# output.net
KiCad netlist of a schematic drawn in Altium Designer
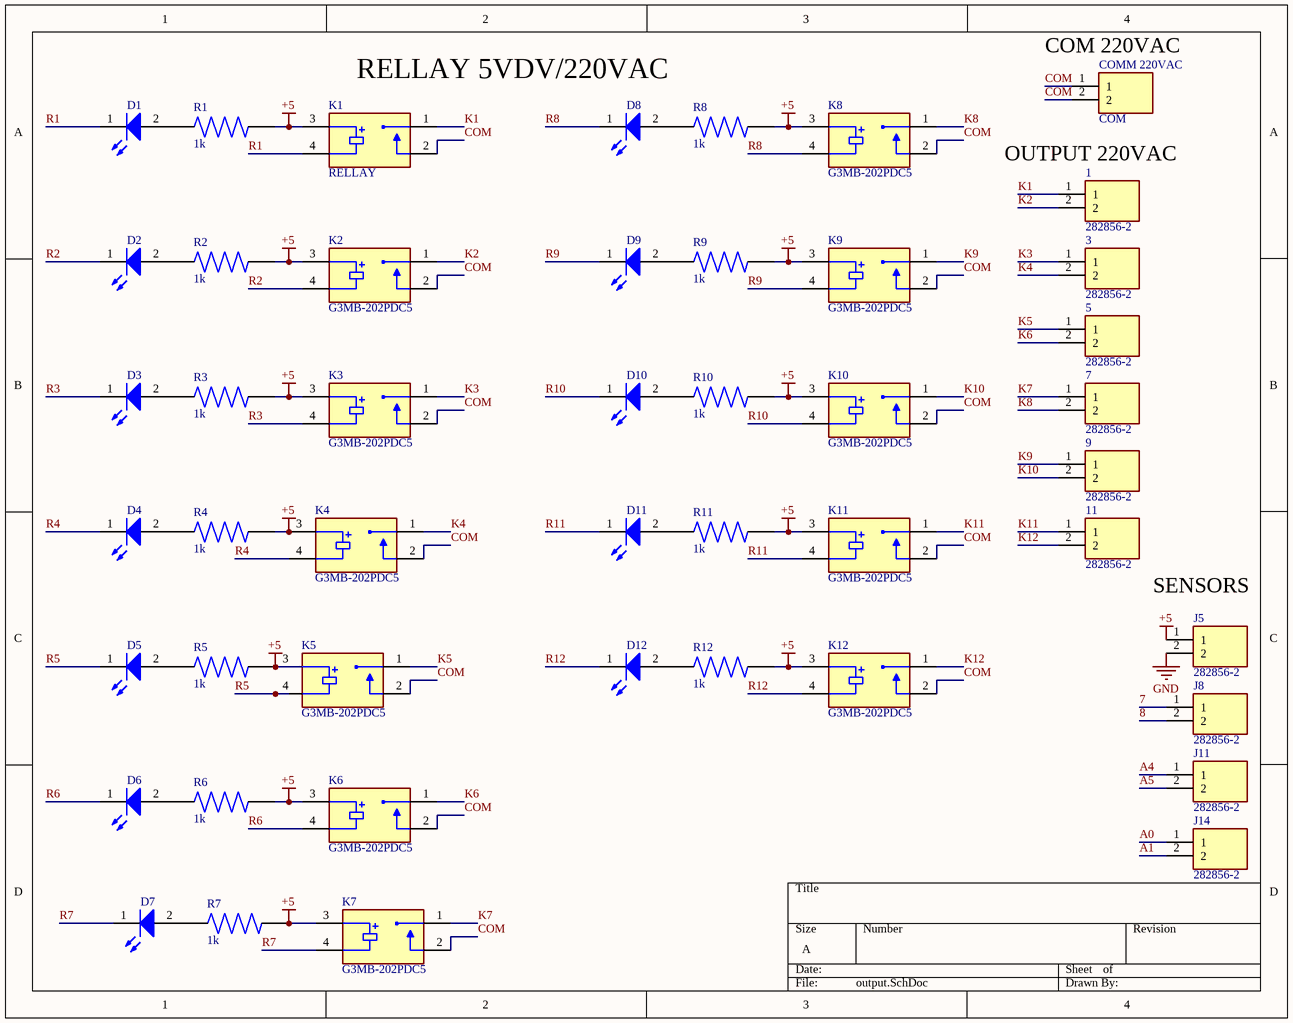
[diagram p0: output.SchDoc]

(export (version "E")
  (design (tool "Eeschema 10.0.6"))
  (components
    (comp (ref "1")
      (value "282856-2")
      (footprint "TE_282856-2")
      (description "TERMI-BLOK PCB MOUNT 2P")
      (fields (field (name "MF") "TE Connectivity"))
      (libsource (lib "input") (part "282856-2"))
    )
    (comp (ref "3")
      (value "282856-2")
      (footprint "TE_282856-2")
      (description "TERMI-BLOK PCB MOUNT 2P")
      (fields (field (name "MF") "TE Connectivity"))
      (libsource (lib "input") (part "282856-2"))
    )
    (comp (ref "5")
      (value "282856-2")
      (footprint "TE_282856-2")
      (description "TERMI-BLOK PCB MOUNT 2P")
      (fields (field (name "MF") "TE Connectivity"))
      (libsource (lib "input") (part "282856-2"))
    )
    (comp (ref "7")
      (value "282856-2")
      (footprint "TE_282856-2")
      (description "TERMI-BLOK PCB MOUNT 2P")
      (fields (field (name "MF") "TE Connectivity"))
      (libsource (lib "input") (part "282856-2"))
    )
    (comp (ref "9")
      (value "282856-2")
      (footprint "TE_282856-2")
      (description "TERMI-BLOK PCB MOUNT 2P")
      (fields (field (name "MF") "TE Connectivity"))
      (libsource (lib "input") (part "282856-2"))
    )
    (comp (ref "11")
      (value "282856-2")
      (footprint "TE_282856-2")
      (description "TERMI-BLOK PCB MOUNT 2P")
      (fields (field (name "MF") "TE Connectivity"))
      (libsource (lib "input") (part "282856-2"))
    )
    (comp (ref "COMM 220VAC")
      (value "COM")
      (footprint "TE_282856-2")
      (description "TERMI-BLOK PCB MOUNT 2P")
      (fields (field (name "MP") "282856-2") (field (name "MF") "TE Connectivity"))
      (libsource (lib "input") (part "282856-2"))
    )
    (comp (ref "D1")
      (value "Infrared, 1.4V, 140°")
      (footprint "WL-SICW_0805_L2W1.3H0.8")
      (description "WL-SICW SMT Chip LED Infrared Waterclear, size 0805, Infrared, 1.4V, 140°")
      (fields
        (field (name "MANUFACTURER PART NUMBER") "15408085BA400")
        (field (name "MANUFACTURER") "Wurth Elektronik")
      )
      (libsource (lib "input") (part "15408085BA400"))
    )
    (comp (ref "D2")
      (value "Infrared, 1.4V, 140°")
      (footprint "WL-SICW_0805_L2W1.3H0.8")
      (description "WL-SICW SMT Chip LED Infrared Waterclear, size 0805, Infrared, 1.4V, 140°")
      (fields
        (field (name "MANUFACTURER PART NUMBER") "15408085BA400")
        (field (name "MANUFACTURER") "Wurth Elektronik")
      )
      (libsource (lib "input") (part "15408085BA400"))
    )
    (comp (ref "D3")
      (value "Infrared, 1.4V, 140°")
      (footprint "WL-SICW_0805_L2W1.3H0.8")
      (description "WL-SICW SMT Chip LED Infrared Waterclear, size 0805, Infrared, 1.4V, 140°")
      (fields
        (field (name "MANUFACTURER PART NUMBER") "15408085BA400")
        (field (name "MANUFACTURER") "Wurth Elektronik")
      )
      (libsource (lib "input") (part "15408085BA400"))
    )
    (comp (ref "D4")
      (value "Infrared, 1.4V, 140°")
      (footprint "WL-SICW_0805_L2W1.3H0.8")
      (description "WL-SICW SMT Chip LED Infrared Waterclear, size 0805, Infrared, 1.4V, 140°")
      (fields
        (field (name "MANUFACTURER PART NUMBER") "15408085BA400")
        (field (name "MANUFACTURER") "Wurth Elektronik")
      )
      (libsource (lib "input") (part "15408085BA400"))
    )
    (comp (ref "D5")
      (value "Infrared, 1.4V, 140°")
      (footprint "WL-SICW_0805_L2W1.3H0.8")
      (description "WL-SICW SMT Chip LED Infrared Waterclear, size 0805, Infrared, 1.4V, 140°")
      (fields
        (field (name "MANUFACTURER PART NUMBER") "15408085BA400")
        (field (name "MANUFACTURER") "Wurth Elektronik")
      )
      (libsource (lib "input") (part "15408085BA400"))
    )
    (comp (ref "D6")
      (value "Infrared, 1.4V, 140°")
      (footprint "WL-SICW_0805_L2W1.3H0.8")
      (description "WL-SICW SMT Chip LED Infrared Waterclear, size 0805, Infrared, 1.4V, 140°")
      (fields
        (field (name "MANUFACTURER PART NUMBER") "15408085BA400")
        (field (name "MANUFACTURER") "Wurth Elektronik")
      )
      (libsource (lib "input") (part "15408085BA400"))
    )
    (comp (ref "D7")
      (value "Infrared, 1.4V, 140°")
      (footprint "WL-SICW_0805_L2W1.3H0.8")
      (description "WL-SICW SMT Chip LED Infrared Waterclear, size 0805, Infrared, 1.4V, 140°")
      (fields
        (field (name "MANUFACTURER PART NUMBER") "15408085BA400")
        (field (name "MANUFACTURER") "Wurth Elektronik")
      )
      (libsource (lib "input") (part "15408085BA400"))
    )
    (comp (ref "D8")
      (value "Infrared, 1.4V, 140°")
      (footprint "WL-SICW_0805_L2W1.3H0.8")
      (description "WL-SICW SMT Chip LED Infrared Waterclear, size 0805, Infrared, 1.4V, 140°")
      (fields
        (field (name "MANUFACTURER PART NUMBER") "15408085BA400")
        (field (name "MANUFACTURER") "Wurth Elektronik")
      )
      (libsource (lib "input") (part "15408085BA400"))
    )
    (comp (ref "D9")
      (value "Infrared, 1.4V, 140°")
      (footprint "WL-SICW_0805_L2W1.3H0.8")
      (description "WL-SICW SMT Chip LED Infrared Waterclear, size 0805, Infrared, 1.4V, 140°")
      (fields
        (field (name "MANUFACTURER PART NUMBER") "15408085BA400")
        (field (name "MANUFACTURER") "Wurth Elektronik")
      )
      (libsource (lib "input") (part "15408085BA400"))
    )
    (comp (ref "D10")
      (value "Infrared, 1.4V, 140°")
      (footprint "WL-SICW_0805_L2W1.3H0.8")
      (description "WL-SICW SMT Chip LED Infrared Waterclear, size 0805, Infrared, 1.4V, 140°")
      (fields
        (field (name "MANUFACTURER PART NUMBER") "15408085BA400")
        (field (name "MANUFACTURER") "Wurth Elektronik")
      )
      (libsource (lib "input") (part "15408085BA400"))
    )
    (comp (ref "D11")
      (value "Infrared, 1.4V, 140°")
      (footprint "WL-SICW_0805_L2W1.3H0.8")
      (description "WL-SICW SMT Chip LED Infrared Waterclear, size 0805, Infrared, 1.4V, 140°")
      (fields
        (field (name "MANUFACTURER PART NUMBER") "15408085BA400")
        (field (name "MANUFACTURER") "Wurth Elektronik")
      )
      (libsource (lib "input") (part "15408085BA400"))
    )
    (comp (ref "D12")
      (value "Infrared, 1.4V, 140°")
      (footprint "WL-SICW_0805_L2W1.3H0.8")
      (description "WL-SICW SMT Chip LED Infrared Waterclear, size 0805, Infrared, 1.4V, 140°")
      (fields
        (field (name "MANUFACTURER PART NUMBER") "15408085BA400")
        (field (name "MANUFACTURER") "Wurth Elektronik")
      )
      (libsource (lib "input") (part "15408085BA400"))
    )
    (comp (ref "J5")
      (value "282856-2")
      (footprint "TE_282856-2")
      (description "TERMI-BLOK PCB MOUNT 2P")
      (fields (field (name "MF") "TE Connectivity"))
      (libsource (lib "input") (part "282856-2"))
    )
    (comp (ref "J8")
      (value "282856-2")
      (footprint "TE_282856-2")
      (description "TERMI-BLOK PCB MOUNT 2P")
      (fields (field (name "MF") "TE Connectivity"))
      (libsource (lib "input") (part "282856-2"))
    )
    (comp (ref "J11")
      (value "282856-2")
      (footprint "TE_282856-2")
      (description "TERMI-BLOK PCB MOUNT 2P")
      (fields (field (name "MF") "TE Connectivity"))
      (libsource (lib "input") (part "282856-2"))
    )
    (comp (ref "J14")
      (value "282856-2")
      (footprint "TE_282856-2")
      (description "TERMI-BLOK PCB MOUNT 2P")
      (fields (field (name "MF") "TE Connectivity"))
      (libsource (lib "input") (part "282856-2"))
    )
    (comp (ref "K1")
      (value "RELLAY")
      (footprint "control:RELAY_G3MB-202PDC5")
      (description "Solid State SPST-NO (1 Form A) 4-SIP")
      (fields (field (name "MP") "G3MB-202P DC5") (field (name "MF") "Omron Automation"))
      (libsource (lib "control") (part "G3MB-202PDC5"))
    )
    (comp (ref "K2")
      (value "G3MB-202PDC5")
      (footprint "control:RELAY_G3MB-202PDC5")
      (description "Solid State SPST-NO (1 Form A) 4-SIP")
      (fields (field (name "MP") "G3MB-202P DC5") (field (name "MF") "Omron Automation"))
      (libsource (lib "control") (part "G3MB-202PDC5"))
    )
    (comp (ref "K3")
      (value "G3MB-202PDC5")
      (footprint "control:RELAY_G3MB-202PDC5")
      (description "Solid State SPST-NO (1 Form A) 4-SIP")
      (fields (field (name "MP") "G3MB-202P DC5") (field (name "MF") "Omron Automation"))
      (libsource (lib "control") (part "G3MB-202PDC5"))
    )
    (comp (ref "K4")
      (value "G3MB-202PDC5")
      (footprint "control:RELAY_G3MB-202PDC5")
      (description "Solid State SPST-NO (1 Form A) 4-SIP")
      (fields (field (name "MP") "G3MB-202P DC5") (field (name "MF") "Omron Automation"))
      (libsource (lib "control") (part "G3MB-202PDC5"))
    )
    (comp (ref "K5")
      (value "G3MB-202PDC5")
      (footprint "control:RELAY_G3MB-202PDC5")
      (description "Solid State SPST-NO (1 Form A) 4-SIP")
      (fields (field (name "MP") "G3MB-202P DC5") (field (name "MF") "Omron Automation"))
      (libsource (lib "control") (part "G3MB-202PDC5"))
    )
    (comp (ref "K6")
      (value "G3MB-202PDC5")
      (footprint "control:RELAY_G3MB-202PDC5")
      (description "Solid State SPST-NO (1 Form A) 4-SIP")
      (fields (field (name "MP") "G3MB-202P DC5") (field (name "MF") "Omron Automation"))
      (libsource (lib "control") (part "G3MB-202PDC5"))
    )
    (comp (ref "K7")
      (value "G3MB-202PDC5")
      (footprint "control:RELAY_G3MB-202PDC5")
      (description "Solid State SPST-NO (1 Form A) 4-SIP")
      (fields (field (name "MP") "G3MB-202P DC5") (field (name "MF") "Omron Automation"))
      (libsource (lib "control") (part "G3MB-202PDC5"))
    )
    (comp (ref "K8")
      (value "G3MB-202PDC5")
      (footprint "control:RELAY_G3MB-202PDC5")
      (description "Solid State SPST-NO (1 Form A) 4-SIP")
      (fields (field (name "MP") "G3MB-202P DC5") (field (name "MF") "Omron Automation"))
      (libsource (lib "control") (part "G3MB-202PDC5"))
    )
    (comp (ref "K9")
      (value "G3MB-202PDC5")
      (footprint "control:RELAY_G3MB-202PDC5")
      (description "Solid State SPST-NO (1 Form A) 4-SIP")
      (fields (field (name "MP") "G3MB-202P DC5") (field (name "MF") "Omron Automation"))
      (libsource (lib "control") (part "G3MB-202PDC5"))
    )
    (comp (ref "K10")
      (value "G3MB-202PDC5")
      (footprint "control:RELAY_G3MB-202PDC5")
      (description "Solid State SPST-NO (1 Form A) 4-SIP")
      (fields (field (name "MP") "G3MB-202P DC5") (field (name "MF") "Omron Automation"))
      (libsource (lib "control") (part "G3MB-202PDC5"))
    )
    (comp (ref "K11")
      (value "G3MB-202PDC5")
      (footprint "control:RELAY_G3MB-202PDC5")
      (description "Solid State SPST-NO (1 Form A) 4-SIP")
      (fields (field (name "MP") "G3MB-202P DC5") (field (name "MF") "Omron Automation"))
      (libsource (lib "control") (part "G3MB-202PDC5"))
    )
    (comp (ref "K12")
      (value "G3MB-202PDC5")
      (footprint "control:RELAY_G3MB-202PDC5")
      (description "Solid State SPST-NO (1 Form A) 4-SIP")
      (fields (field (name "MP") "G3MB-202P DC5") (field (name "MF") "Omron Automation"))
      (libsource (lib "control") (part "G3MB-202PDC5"))
    )
    (comp (ref "R1")
      (value "1k")
      (footprint "RESC3216X70N")
      (description "Res 1206 10 Ohm 5% 1/8W Â±500ppm/Â°C Molded SMD SMD T/R")
      (fields (field (name "TOLERANCE") "5%") (field (name "MP") "FCR1206J10R"))
      (libsource (lib "input") (part "FCR1206J10R"))
    )
    (comp (ref "R2")
      (value "1k")
      (footprint "RESC3216X70N")
      (description "Res 1206 10 Ohm 5% 1/8W Â±500ppm/Â°C Molded SMD SMD T/R")
      (fields (field (name "TOLERANCE") "5%") (field (name "MP") "FCR1206J10R"))
      (libsource (lib "input") (part "FCR1206J10R"))
    )
    (comp (ref "R3")
      (value "1k")
      (footprint "RESC3216X70N")
      (description "Res 1206 10 Ohm 5% 1/8W Â±500ppm/Â°C Molded SMD SMD T/R")
      (fields (field (name "TOLERANCE") "5%") (field (name "MP") "FCR1206J10R"))
      (libsource (lib "input") (part "FCR1206J10R"))
    )
    (comp (ref "R4")
      (value "1k")
      (footprint "RESC3216X70N")
      (description "Res 1206 10 Ohm 5% 1/8W Â±500ppm/Â°C Molded SMD SMD T/R")
      (fields (field (name "TOLERANCE") "5%") (field (name "MP") "FCR1206J10R"))
      (libsource (lib "input") (part "FCR1206J10R"))
    )
    (comp (ref "R5")
      (value "1k")
      (footprint "RESC3216X70N")
      (description "Res 1206 10 Ohm 5% 1/8W Â±500ppm/Â°C Molded SMD SMD T/R")
      (fields (field (name "TOLERANCE") "5%") (field (name "MP") "FCR1206J10R"))
      (libsource (lib "input") (part "FCR1206J10R"))
    )
    (comp (ref "R6")
      (value "1k")
      (footprint "RESC3216X70N")
      (description "Res 1206 10 Ohm 5% 1/8W Â±500ppm/Â°C Molded SMD SMD T/R")
      (fields (field (name "TOLERANCE") "5%") (field (name "MP") "FCR1206J10R"))
      (libsource (lib "input") (part "FCR1206J10R"))
    )
    (comp (ref "R7")
      (value "1k")
      (footprint "RESC3216X70N")
      (description "Res 1206 10 Ohm 5% 1/8W Â±500ppm/Â°C Molded SMD SMD T/R")
      (fields (field (name "TOLERANCE") "5%") (field (name "MP") "FCR1206J10R"))
      (libsource (lib "input") (part "FCR1206J10R"))
    )
    (comp (ref "R8")
      (value "1k")
      (footprint "RESC3216X70N")
      (description "Res 1206 10 Ohm 5% 1/8W Â±500ppm/Â°C Molded SMD SMD T/R")
      (fields (field (name "TOLERANCE") "5%") (field (name "MP") "FCR1206J10R"))
      (libsource (lib "input") (part "FCR1206J10R"))
    )
    (comp (ref "R9")
      (value "1k")
      (footprint "RESC3216X70N")
      (description "Res 1206 10 Ohm 5% 1/8W Â±500ppm/Â°C Molded SMD SMD T/R")
      (fields (field (name "TOLERANCE") "5%") (field (name "MP") "FCR1206J10R"))
      (libsource (lib "input") (part "FCR1206J10R"))
    )
    (comp (ref "R10")
      (value "1k")
      (footprint "RESC3216X70N")
      (description "Res 1206 10 Ohm 5% 1/8W Â±500ppm/Â°C Molded SMD SMD T/R")
      (fields (field (name "TOLERANCE") "5%") (field (name "MP") "FCR1206J10R"))
      (libsource (lib "input") (part "FCR1206J10R"))
    )
    (comp (ref "R11")
      (value "1k")
      (footprint "RESC3216X70N")
      (description "Res 1206 10 Ohm 5% 1/8W Â±500ppm/Â°C Molded SMD SMD T/R")
      (fields (field (name "TOLERANCE") "5%") (field (name "MP") "FCR1206J10R"))
      (libsource (lib "input") (part "FCR1206J10R"))
    )
    (comp (ref "R12")
      (value "1k")
      (footprint "RESC3216X70N")
      (description "Res 1206 10 Ohm 5% 1/8W Â±500ppm/Â°C Molded SMD SMD T/R")
      (fields (field (name "TOLERANCE") "5%") (field (name "MP") "FCR1206J10R"))
      (libsource (lib "input") (part "FCR1206J10R"))
    )
  )
  (nets
    (net (code "1") (name "+5") (class "Default")
      (node (ref "J5") (pin "1") (pinfunction "1_1") (pintype "passive"))
      (node (ref "K1") (pin "3") (pinfunction "3_3") (pintype "passive"))
      (node (ref "K10") (pin "3") (pinfunction "3_3") (pintype "passive"))
      (node (ref "K11") (pin "3") (pinfunction "3_3") (pintype "passive"))
      (node (ref "K12") (pin "3") (pinfunction "3_3") (pintype "passive"))
      (node (ref "K2") (pin "3") (pinfunction "3_3") (pintype "passive"))
      (node (ref "K3") (pin "3") (pinfunction "3_3") (pintype "passive"))
      (node (ref "K4") (pin "3") (pinfunction "3_3") (pintype "passive"))
      (node (ref "K5") (pin "3") (pinfunction "3_3") (pintype "passive"))
      (node (ref "K6") (pin "3") (pinfunction "3_3") (pintype "passive"))
      (node (ref "K7") (pin "3") (pinfunction "3_3") (pintype "passive"))
      (node (ref "K8") (pin "3") (pinfunction "3_3") (pintype "passive"))
      (node (ref "K9") (pin "3") (pinfunction "3_3") (pintype "passive"))
      (node (ref "R1") (pin "2") (pinfunction "2_2") (pintype "passive"))
      (node (ref "R10") (pin "2") (pinfunction "2_2") (pintype "passive"))
      (node (ref "R11") (pin "2") (pinfunction "2_2") (pintype "passive"))
      (node (ref "R12") (pin "2") (pinfunction "2_2") (pintype "passive"))
      (node (ref "R2") (pin "2") (pinfunction "2_2") (pintype "passive"))
      (node (ref "R3") (pin "2") (pinfunction "2_2") (pintype "passive"))
      (node (ref "R4") (pin "2") (pinfunction "2_2") (pintype "passive"))
      (node (ref "R5") (pin "2") (pinfunction "2_2") (pintype "passive"))
      (node (ref "R6") (pin "2") (pinfunction "2_2") (pintype "passive"))
      (node (ref "R7") (pin "2") (pinfunction "2_2") (pintype "passive"))
      (node (ref "R8") (pin "2") (pinfunction "2_2") (pintype "passive"))
      (node (ref "R9") (pin "2") (pinfunction "2_2") (pintype "passive"))
    )
    (net (code "2") (name "/7") (class "Default")
      (node (ref "J8") (pin "1") (pinfunction "1_1") (pintype "passive"))
    )
    (net (code "3") (name "/8") (class "Default")
      (node (ref "J8") (pin "2") (pinfunction "2_2") (pintype "passive"))
    )
    (net (code "4") (name "/A0") (class "Default")
      (node (ref "J14") (pin "1") (pinfunction "1_1") (pintype "passive"))
    )
    (net (code "5") (name "/A1") (class "Default")
      (node (ref "J14") (pin "2") (pinfunction "2_2") (pintype "passive"))
    )
    (net (code "6") (name "/A4") (class "Default")
      (node (ref "J11") (pin "1") (pinfunction "1_1") (pintype "passive"))
    )
    (net (code "7") (name "/A5") (class "Default")
      (node (ref "J11") (pin "2") (pinfunction "2_2") (pintype "passive"))
    )
    (net (code "8") (name "/COM") (class "Default")
      (node (ref "COMM 220VAC") (pin "1") (pinfunction "1_1") (pintype "passive"))
      (node (ref "COMM 220VAC") (pin "2") (pinfunction "2_2") (pintype "passive"))
      (node (ref "K1") (pin "2") (pinfunction "2_2") (pintype "passive"))
      (node (ref "K10") (pin "2") (pinfunction "2_2") (pintype "passive"))
      (node (ref "K11") (pin "2") (pinfunction "2_2") (pintype "passive"))
      (node (ref "K12") (pin "2") (pinfunction "2_2") (pintype "passive"))
      (node (ref "K2") (pin "2") (pinfunction "2_2") (pintype "passive"))
      (node (ref "K3") (pin "2") (pinfunction "2_2") (pintype "passive"))
      (node (ref "K4") (pin "2") (pinfunction "2_2") (pintype "passive"))
      (node (ref "K5") (pin "2") (pinfunction "2_2") (pintype "passive"))
      (node (ref "K6") (pin "2") (pinfunction "2_2") (pintype "passive"))
      (node (ref "K7") (pin "2") (pinfunction "2_2") (pintype "passive"))
      (node (ref "K8") (pin "2") (pinfunction "2_2") (pintype "passive"))
      (node (ref "K9") (pin "2") (pinfunction "2_2") (pintype "passive"))
    )
    (net (code "9") (name "/K1") (class "Default")
      (node (ref "1") (pin "1") (pinfunction "1_1") (pintype "passive"))
      (node (ref "K1") (pin "1") (pinfunction "1_1") (pintype "passive"))
    )
    (net (code "10") (name "/K2") (class "Default")
      (node (ref "1") (pin "2") (pinfunction "2_2") (pintype "passive"))
      (node (ref "K2") (pin "1") (pinfunction "1_1") (pintype "passive"))
    )
    (net (code "11") (name "/K3") (class "Default")
      (node (ref "3") (pin "1") (pinfunction "1_1") (pintype "passive"))
      (node (ref "K3") (pin "1") (pinfunction "1_1") (pintype "passive"))
    )
    (net (code "12") (name "/K4") (class "Default")
      (node (ref "3") (pin "2") (pinfunction "2_2") (pintype "passive"))
      (node (ref "K4") (pin "1") (pinfunction "1_1") (pintype "passive"))
    )
    (net (code "13") (name "/K5") (class "Default")
      (node (ref "5") (pin "1") (pinfunction "1_1") (pintype "passive"))
      (node (ref "K5") (pin "1") (pinfunction "1_1") (pintype "passive"))
    )
    (net (code "14") (name "/K6") (class "Default")
      (node (ref "5") (pin "2") (pinfunction "2_2") (pintype "passive"))
      (node (ref "K6") (pin "1") (pinfunction "1_1") (pintype "passive"))
    )
    (net (code "15") (name "/K7") (class "Default")
      (node (ref "7") (pin "1") (pinfunction "1_1") (pintype "passive"))
      (node (ref "K7") (pin "1") (pinfunction "1_1") (pintype "passive"))
    )
    (net (code "16") (name "/K8") (class "Default")
      (node (ref "7") (pin "2") (pinfunction "2_2") (pintype "passive"))
      (node (ref "K8") (pin "1") (pinfunction "1_1") (pintype "passive"))
    )
    (net (code "17") (name "/K9") (class "Default")
      (node (ref "9") (pin "1") (pinfunction "1_1") (pintype "passive"))
      (node (ref "K9") (pin "1") (pinfunction "1_1") (pintype "passive"))
    )
    (net (code "18") (name "/K10") (class "Default")
      (node (ref "9") (pin "2") (pinfunction "2_2") (pintype "passive"))
      (node (ref "K10") (pin "1") (pinfunction "1_1") (pintype "passive"))
    )
    (net (code "19") (name "/K11") (class "Default")
      (node (ref "11") (pin "1") (pinfunction "1_1") (pintype "passive"))
      (node (ref "K11") (pin "1") (pinfunction "1_1") (pintype "passive"))
    )
    (net (code "20") (name "/K12") (class "Default")
      (node (ref "11") (pin "2") (pinfunction "2_2") (pintype "passive"))
      (node (ref "K12") (pin "1") (pinfunction "1_1") (pintype "passive"))
    )
    (net (code "21") (name "/R1") (class "Default")
      (node (ref "D1") (pin "1") (pinfunction "K_1") (pintype "passive"))
      (node (ref "K1") (pin "4") (pinfunction "4_4") (pintype "passive"))
    )
    (net (code "22") (name "/R2") (class "Default")
      (node (ref "D2") (pin "1") (pinfunction "K_1") (pintype "passive"))
      (node (ref "K2") (pin "4") (pinfunction "4_4") (pintype "passive"))
    )
    (net (code "23") (name "/R3") (class "Default")
      (node (ref "D3") (pin "1") (pinfunction "K_1") (pintype "passive"))
      (node (ref "K3") (pin "4") (pinfunction "4_4") (pintype "passive"))
    )
    (net (code "24") (name "/R4") (class "Default")
      (node (ref "D4") (pin "1") (pinfunction "K_1") (pintype "passive"))
      (node (ref "K4") (pin "4") (pinfunction "4_4") (pintype "passive"))
    )
    (net (code "25") (name "/R5") (class "Default")
      (node (ref "D5") (pin "1") (pinfunction "K_1") (pintype "passive"))
      (node (ref "K5") (pin "4") (pinfunction "4_4") (pintype "passive"))
    )
    (net (code "26") (name "/R6") (class "Default")
      (node (ref "D6") (pin "1") (pinfunction "K_1") (pintype "passive"))
      (node (ref "K6") (pin "4") (pinfunction "4_4") (pintype "passive"))
    )
    (net (code "27") (name "/R7") (class "Default")
      (node (ref "D7") (pin "1") (pinfunction "K_1") (pintype "passive"))
      (node (ref "K7") (pin "4") (pinfunction "4_4") (pintype "passive"))
    )
    (net (code "28") (name "/R8") (class "Default")
      (node (ref "D8") (pin "1") (pinfunction "K_1") (pintype "passive"))
      (node (ref "K8") (pin "4") (pinfunction "4_4") (pintype "passive"))
    )
    (net (code "29") (name "/R9") (class "Default")
      (node (ref "D9") (pin "1") (pinfunction "K_1") (pintype "passive"))
      (node (ref "K9") (pin "4") (pinfunction "4_4") (pintype "passive"))
    )
    (net (code "30") (name "/R10") (class "Default")
      (node (ref "D10") (pin "1") (pinfunction "K_1") (pintype "passive"))
      (node (ref "K10") (pin "4") (pinfunction "4_4") (pintype "passive"))
    )
    (net (code "31") (name "/R11") (class "Default")
      (node (ref "D11") (pin "1") (pinfunction "K_1") (pintype "passive"))
      (node (ref "K11") (pin "4") (pinfunction "4_4") (pintype "passive"))
    )
    (net (code "32") (name "/R12") (class "Default")
      (node (ref "D12") (pin "1") (pinfunction "K_1") (pintype "passive"))
      (node (ref "K12") (pin "4") (pinfunction "4_4") (pintype "passive"))
    )
    (net (code "33") (name "GND") (class "Default")
      (node (ref "J5") (pin "2") (pinfunction "2_2") (pintype "passive"))
    )
    (net (code "34") (name "Net-(D1-A)") (class "Default")
      (node (ref "D1") (pin "2") (pinfunction "A_2") (pintype "passive"))
      (node (ref "R1") (pin "1") (pinfunction "1_1") (pintype "passive"))
    )
    (net (code "35") (name "Net-(D2-A)") (class "Default")
      (node (ref "D2") (pin "2") (pinfunction "A_2") (pintype "passive"))
      (node (ref "R2") (pin "1") (pinfunction "1_1") (pintype "passive"))
    )
    (net (code "36") (name "Net-(D3-A)") (class "Default")
      (node (ref "D3") (pin "2") (pinfunction "A_2") (pintype "passive"))
      (node (ref "R3") (pin "1") (pinfunction "1_1") (pintype "passive"))
    )
    (net (code "37") (name "Net-(D4-A)") (class "Default")
      (node (ref "D4") (pin "2") (pinfunction "A_2") (pintype "passive"))
      (node (ref "R4") (pin "1") (pinfunction "1_1") (pintype "passive"))
    )
    (net (code "38") (name "Net-(D5-A)") (class "Default")
      (node (ref "D5") (pin "2") (pinfunction "A_2") (pintype "passive"))
      (node (ref "R5") (pin "1") (pinfunction "1_1") (pintype "passive"))
    )
    (net (code "39") (name "Net-(D6-A)") (class "Default")
      (node (ref "D6") (pin "2") (pinfunction "A_2") (pintype "passive"))
      (node (ref "R6") (pin "1") (pinfunction "1_1") (pintype "passive"))
    )
    (net (code "40") (name "Net-(D7-A)") (class "Default")
      (node (ref "D7") (pin "2") (pinfunction "A_2") (pintype "passive"))
      (node (ref "R7") (pin "1") (pinfunction "1_1") (pintype "passive"))
    )
    (net (code "41") (name "Net-(D8-A)") (class "Default")
      (node (ref "D8") (pin "2") (pinfunction "A_2") (pintype "passive"))
      (node (ref "R8") (pin "1") (pinfunction "1_1") (pintype "passive"))
    )
    (net (code "42") (name "Net-(D9-A)") (class "Default")
      (node (ref "D9") (pin "2") (pinfunction "A_2") (pintype "passive"))
      (node (ref "R9") (pin "1") (pinfunction "1_1") (pintype "passive"))
    )
    (net (code "43") (name "Net-(D10-A)") (class "Default")
      (node (ref "D10") (pin "2") (pinfunction "A_2") (pintype "passive"))
      (node (ref "R10") (pin "1") (pinfunction "1_1") (pintype "passive"))
    )
    (net (code "44") (name "Net-(D11-A)") (class "Default")
      (node (ref "D11") (pin "2") (pinfunction "A_2") (pintype "passive"))
      (node (ref "R11") (pin "1") (pinfunction "1_1") (pintype "passive"))
    )
    (net (code "45") (name "Net-(D12-A)") (class "Default")
      (node (ref "D12") (pin "2") (pinfunction "A_2") (pintype "passive"))
      (node (ref "R12") (pin "1") (pinfunction "1_1") (pintype "passive"))
    )
  )
)
